# 28_Pins_Project_V1I2.net
KiCad netlist of a schematic drawn in Altium Designer
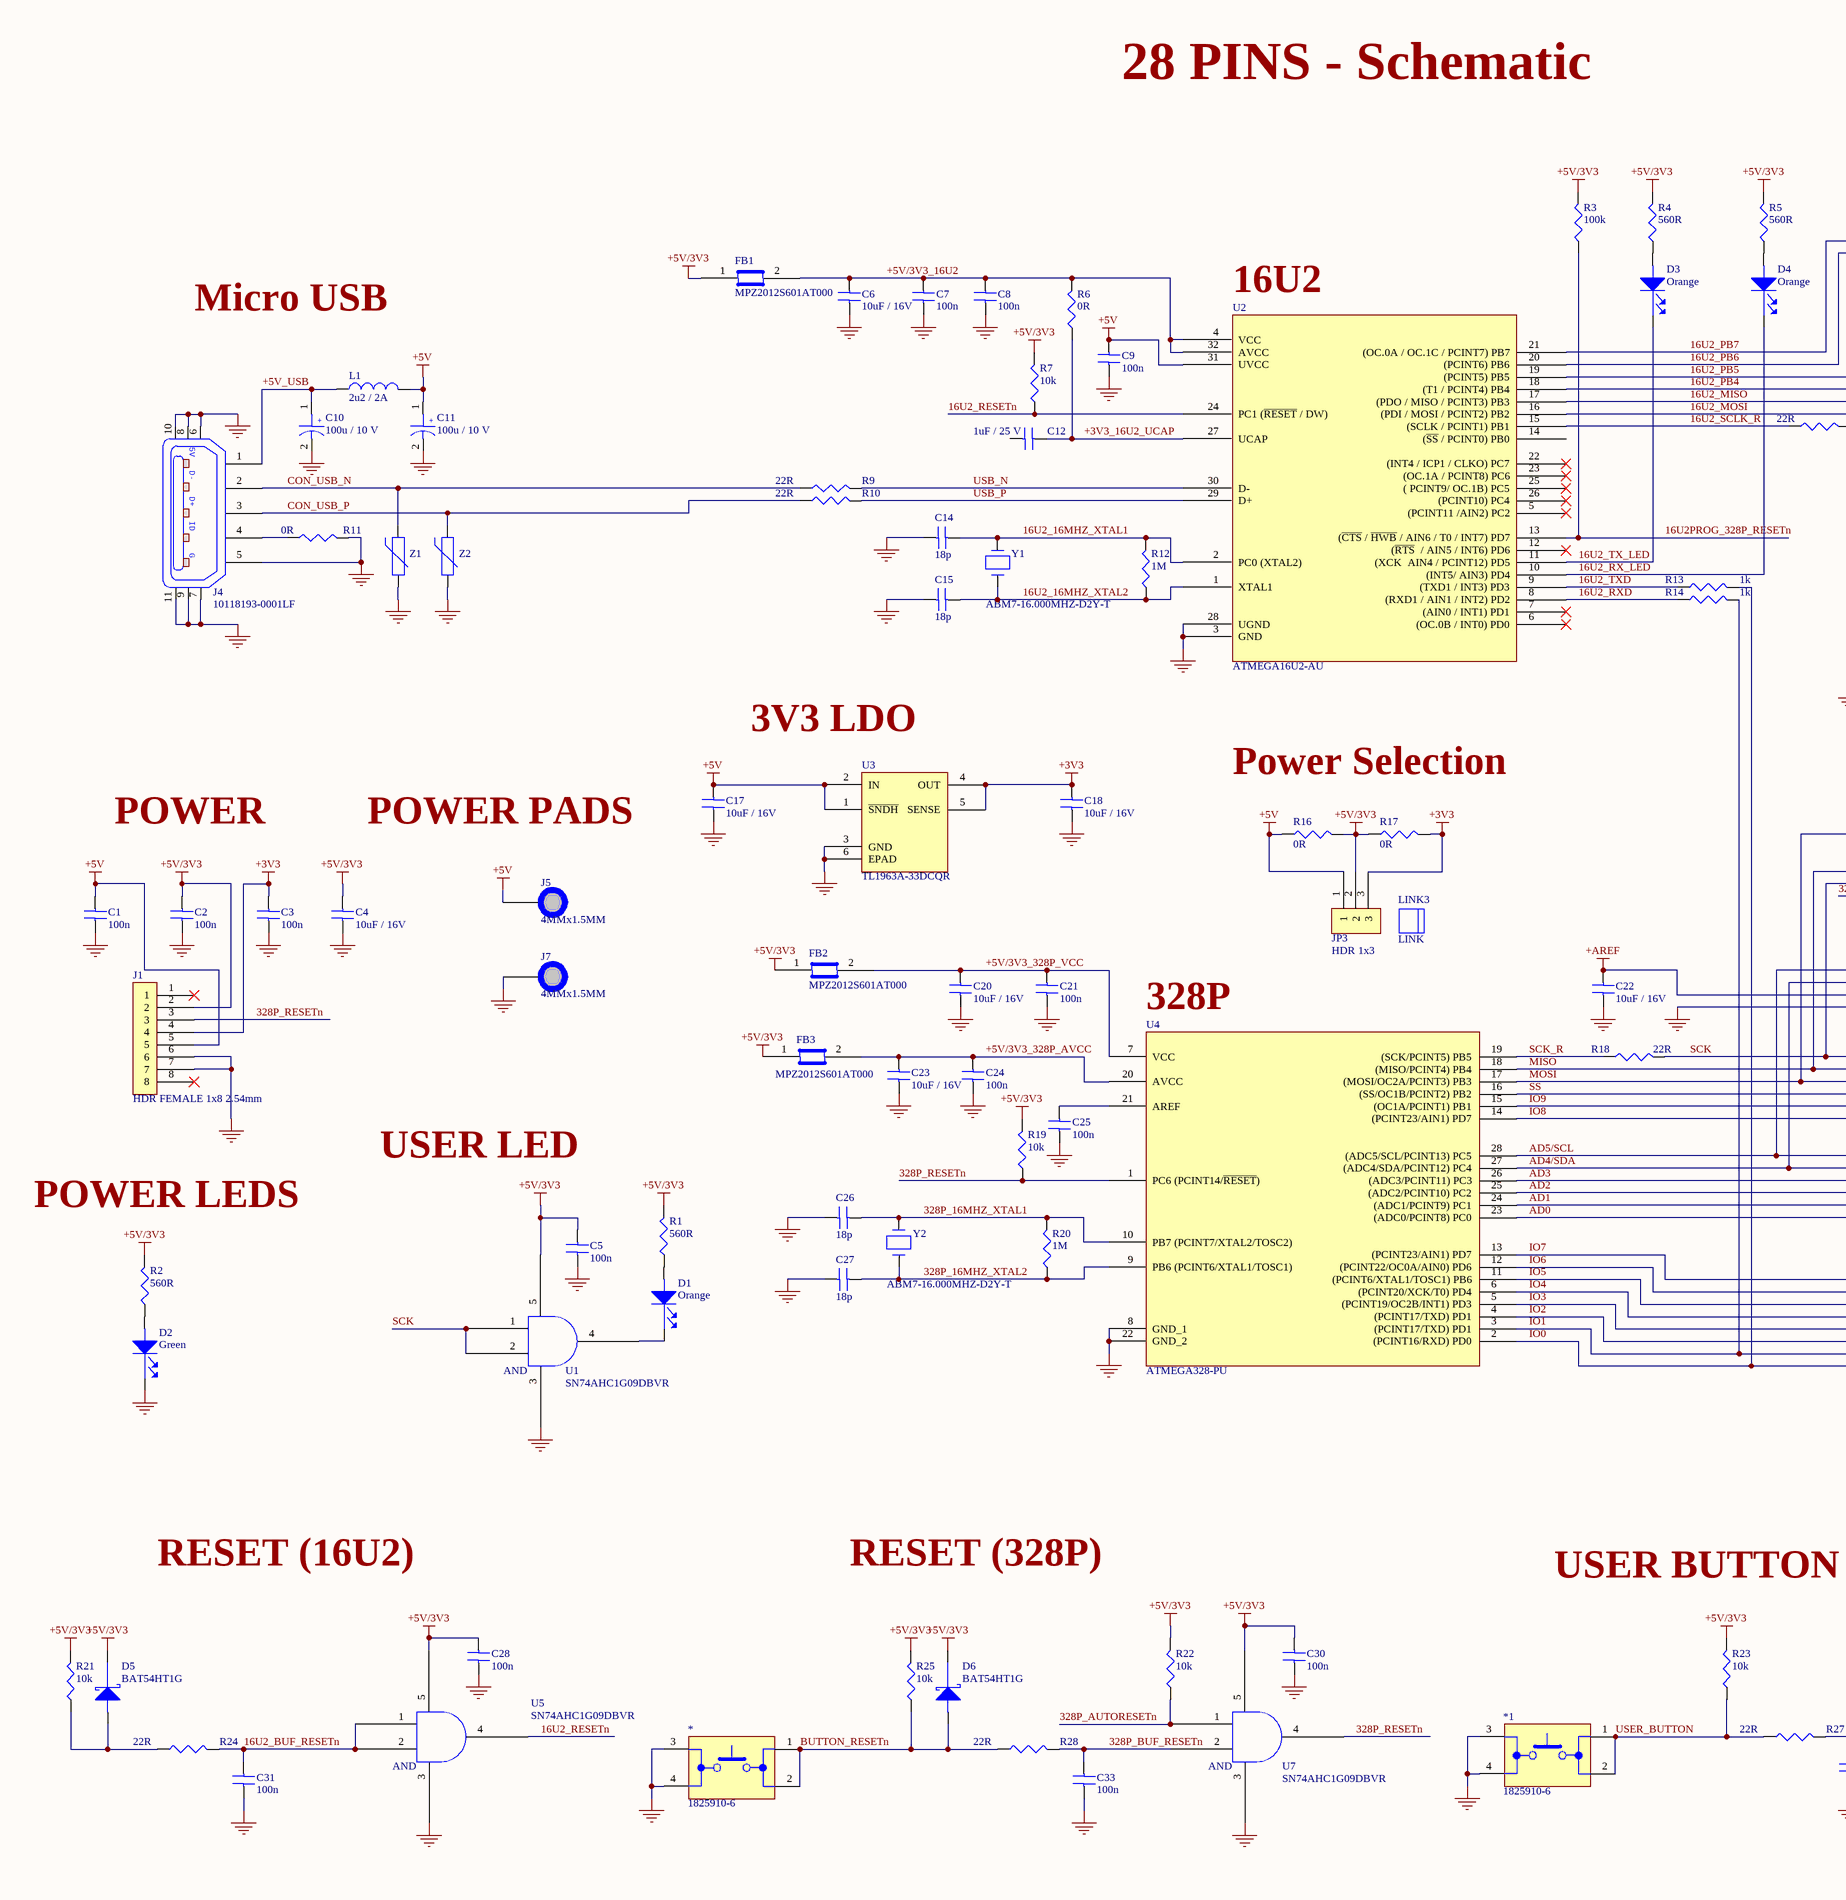
[diagram p0: 28_Pins_Project_V1I2.SchDoc, left]
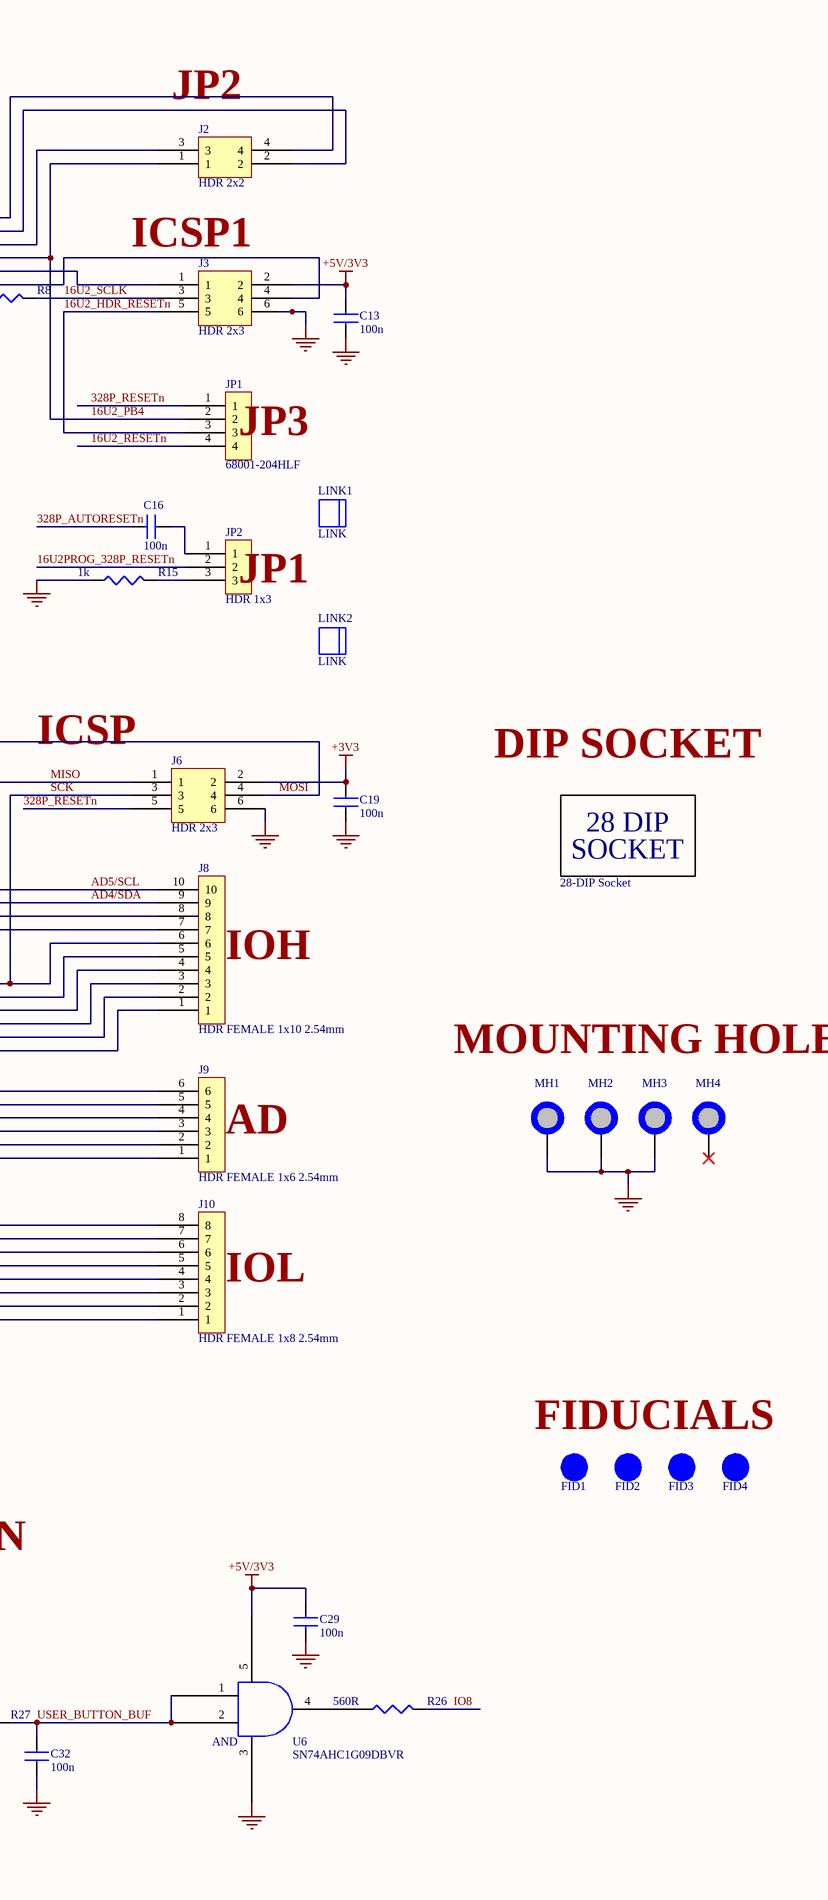
[diagram p1: 28_Pins_Project_V1I2.SchDoc, right]

(export (version "E")
  (design (tool "Eeschema 10.0.6"))
  (components
    (comp (ref "*")
      (value "1825910-6")
      (footprint "1825910-6")
      (description "6X6, H5,  160G TAC.SWITCH")
      (fields (field (name "MANUFACTURER") "TE Connectivity Alcoswitch"))
      (libsource (lib "28_Pins_Project_V1I2") (part "1825910-6"))
    )
    (comp (ref "*1")
      (value "1825910-6")
      (footprint "1825910-6")
      (description "6X6, H5,  160G TAC.SWITCH")
      (fields (field (name "MANUFACTURER") "TE Connectivity Alcoswitch"))
      (libsource (lib "28_Pins_Project_V1I2") (part "1825910-6"))
    )
    (comp (ref "C1")
      (value "100n")
      (footprint "C0805")
      (fields
        (field (name "MANUFACTURER") "TDK")
        (field (name "MANUFACTURER PART NUMBER") "C2012X7R1H104K085AA")
        (field (name "TOLERANCE") "10%")
      )
      (libsource (lib "28_Pins_Project_V1I2") (part "C2012X7R1H104K085AA"))
    )
    (comp (ref "C2")
      (value "100n")
      (footprint "C0805")
      (fields
        (field (name "MANUFACTURER") "TDK")
        (field (name "MANUFACTURER PART NUMBER") "C2012X7R1H104K085AA")
        (field (name "TOLERANCE") "10%")
      )
      (libsource (lib "28_Pins_Project_V1I2") (part "C2012X7R1H104K085AA"))
    )
    (comp (ref "C3")
      (value "100n")
      (footprint "C0805")
      (fields
        (field (name "MANUFACTURER") "TDK")
        (field (name "MANUFACTURER PART NUMBER") "C2012X7R1H104K085AA")
        (field (name "TOLERANCE") "10%")
      )
      (libsource (lib "28_Pins_Project_V1I2") (part "C2012X7R1H104K085AA"))
    )
    (comp (ref "C4")
      (value "10uF / 16V")
      (footprint "C0805")
      (fields
        (field (name "MANUFACTURER") "TDK")
        (field (name "MANUFACTURER PART NUMBER") "C2012X5R1C106M125AC")
        (field (name "TOLERANCE") "20%")
      )
      (libsource (lib "28_Pins_Project_V1I2") (part "C2012X5R1C106M125AC"))
    )
    (comp (ref "C5")
      (value "100n")
      (footprint "C0805")
      (fields
        (field (name "MANUFACTURER") "TDK")
        (field (name "MANUFACTURER PART NUMBER") "C2012X7R1H104K085AA")
        (field (name "TOLERANCE") "10%")
      )
      (libsource (lib "28_Pins_Project_V1I2") (part "C2012X7R1H104K085AA"))
    )
    (comp (ref "C6")
      (value "10uF / 16V")
      (footprint "C0805")
      (fields
        (field (name "MANUFACTURER") "TDK")
        (field (name "MANUFACTURER PART NUMBER") "C2012X5R1C106M125AC")
        (field (name "TOLERANCE") "20%")
      )
      (libsource (lib "28_Pins_Project_V1I2") (part "C2012X5R1C106M125AC"))
    )
    (comp (ref "C7")
      (value "100n")
      (footprint "C0805")
      (fields
        (field (name "MANUFACTURER") "TDK")
        (field (name "MANUFACTURER PART NUMBER") "C2012X7R1H104K085AA")
        (field (name "TOLERANCE") "10%")
      )
      (libsource (lib "28_Pins_Project_V1I2") (part "C2012X7R1H104K085AA"))
    )
    (comp (ref "C8")
      (value "100n")
      (footprint "C0805")
      (fields
        (field (name "MANUFACTURER") "TDK")
        (field (name "MANUFACTURER PART NUMBER") "C2012X7R1H104K085AA")
        (field (name "TOLERANCE") "10%")
      )
      (libsource (lib "28_Pins_Project_V1I2") (part "C2012X7R1H104K085AA"))
    )
    (comp (ref "C9")
      (value "100n")
      (footprint "C0805")
      (fields
        (field (name "MANUFACTURER") "TDK")
        (field (name "MANUFACTURER PART NUMBER") "C2012X7R1H104K085AA")
        (field (name "TOLERANCE") "10%")
      )
      (libsource (lib "28_Pins_Project_V1I2") (part "C2012X7R1H104K085AA"))
    )
    (comp (ref "C10")
      (value "100u / 10 V")
      (footprint "C_ALU_C_SIZE")
      (description "CAP ALUM 100UF 20% 10V SMD")
      (fields
        (field (name "MANUFACTURER") "Panasonic")
        (field (name "MANUFACTURER PART NUMBER") "EEE-1AA101WR")
      )
      (libsource (lib "28_Pins_Project_V1I2") (part "EEE-1AA101WR"))
    )
    (comp (ref "C11")
      (value "100u / 10 V")
      (footprint "C_ALU_C_SIZE")
      (description "CAP ALUM 100UF 20% 10V SMD")
      (fields
        (field (name "MANUFACTURER") "Panasonic")
        (field (name "MANUFACTURER PART NUMBER") "EEE-1AA101WR")
      )
      (libsource (lib "28_Pins_Project_V1I2") (part "EEE-1AA101WR"))
    )
    (comp (ref "C12")
      (value "1uF / 25 V")
      (footprint "C0805")
      (fields
        (field (name "MANUFACTURER") "TDK")
        (field (name "MANUFACTURER PART NUMBER") "C2012X5R1E105K125AA")
        (field (name "TOLERANCE") "10%")
      )
      (libsource (lib "28_Pins_Project_V1I2") (part "C2012X5R1E105K125AA"))
    )
    (comp (ref "C13")
      (value "100n")
      (footprint "C0805")
      (fields
        (field (name "MANUFACTURER") "TDK")
        (field (name "MANUFACTURER PART NUMBER") "C2012X7R1H104K085AA")
        (field (name "TOLERANCE") "10%")
      )
      (libsource (lib "28_Pins_Project_V1I2") (part "C2012X7R1H104K085AA"))
    )
    (comp (ref "C14")
      (value "18p")
      (footprint "C0805")
      (description "CAP CER 18PF 50V C0G/NP0 0805")
      (fields
        (field (name "MANUFACTURER") "KEMET")
        (field (name "MANUFACTURER PART NUMBER") "C0805C180J5GACTU")
      )
      (libsource (lib "28_Pins_Project_V1I2") (part "C0805C180J5GACTU"))
    )
    (comp (ref "C15")
      (value "18p")
      (footprint "C0805")
      (description "CAP CER 18PF 50V C0G/NP0 0805")
      (fields
        (field (name "MANUFACTURER") "KEMET")
        (field (name "MANUFACTURER PART NUMBER") "C0805C180J5GACTU")
      )
      (libsource (lib "28_Pins_Project_V1I2") (part "C0805C180J5GACTU"))
    )
    (comp (ref "C16")
      (value "100n")
      (footprint "C0805")
      (fields
        (field (name "MANUFACTURER") "TDK")
        (field (name "MANUFACTURER PART NUMBER") "C2012X7R1H104K085AA")
        (field (name "TOLERANCE") "10%")
      )
      (libsource (lib "28_Pins_Project_V1I2") (part "C2012X7R1H104K085AA"))
    )
    (comp (ref "C17")
      (value "10uF / 16V")
      (footprint "C0805")
      (fields
        (field (name "MANUFACTURER") "TDK")
        (field (name "MANUFACTURER PART NUMBER") "C2012X5R1C106M125AC")
        (field (name "TOLERANCE") "20%")
      )
      (libsource (lib "28_Pins_Project_V1I2") (part "C2012X5R1C106M125AC"))
    )
    (comp (ref "C18")
      (value "10uF / 16V")
      (footprint "C0805")
      (fields
        (field (name "MANUFACTURER") "TDK")
        (field (name "MANUFACTURER PART NUMBER") "C2012X5R1C106M125AC")
        (field (name "TOLERANCE") "20%")
      )
      (libsource (lib "28_Pins_Project_V1I2") (part "C2012X5R1C106M125AC"))
    )
    (comp (ref "C19")
      (value "100n")
      (footprint "C0805")
      (fields
        (field (name "MANUFACTURER") "TDK")
        (field (name "MANUFACTURER PART NUMBER") "C2012X7R1H104K085AA")
        (field (name "TOLERANCE") "10%")
      )
      (libsource (lib "28_Pins_Project_V1I2") (part "C2012X7R1H104K085AA"))
    )
    (comp (ref "C20")
      (value "10uF / 16V")
      (footprint "C0805")
      (fields
        (field (name "MANUFACTURER") "TDK")
        (field (name "MANUFACTURER PART NUMBER") "C2012X5R1C106M125AC")
        (field (name "TOLERANCE") "20%")
      )
      (libsource (lib "28_Pins_Project_V1I2") (part "C2012X5R1C106M125AC"))
    )
    (comp (ref "C21")
      (value "100n")
      (footprint "C0805")
      (fields
        (field (name "MANUFACTURER") "TDK")
        (field (name "MANUFACTURER PART NUMBER") "C2012X7R1H104K085AA")
        (field (name "TOLERANCE") "10%")
      )
      (libsource (lib "28_Pins_Project_V1I2") (part "C2012X7R1H104K085AA"))
    )
    (comp (ref "C22")
      (value "10uF / 16V")
      (footprint "C0805")
      (fields
        (field (name "MANUFACTURER") "TDK")
        (field (name "MANUFACTURER PART NUMBER") "C2012X5R1C106M125AC")
        (field (name "TOLERANCE") "20%")
      )
      (libsource (lib "28_Pins_Project_V1I2") (part "C2012X5R1C106M125AC"))
    )
    (comp (ref "C23")
      (value "10uF / 16V")
      (footprint "C0805")
      (fields
        (field (name "MANUFACTURER") "TDK")
        (field (name "MANUFACTURER PART NUMBER") "C2012X5R1C106M125AC")
        (field (name "TOLERANCE") "20%")
      )
      (libsource (lib "28_Pins_Project_V1I2") (part "C2012X5R1C106M125AC"))
    )
    (comp (ref "C24")
      (value "100n")
      (footprint "C0805")
      (fields
        (field (name "MANUFACTURER") "TDK")
        (field (name "MANUFACTURER PART NUMBER") "C2012X7R1H104K085AA")
        (field (name "TOLERANCE") "10%")
      )
      (libsource (lib "28_Pins_Project_V1I2") (part "C2012X7R1H104K085AA"))
    )
    (comp (ref "C25")
      (value "100n")
      (footprint "C0805")
      (fields
        (field (name "MANUFACTURER") "TDK")
        (field (name "MANUFACTURER PART NUMBER") "C2012X7R1H104K085AA")
        (field (name "TOLERANCE") "10%")
      )
      (libsource (lib "28_Pins_Project_V1I2") (part "C2012X7R1H104K085AA"))
    )
    (comp (ref "C26")
      (value "18p")
      (footprint "C0805")
      (description "CAP CER 18PF 50V C0G/NP0 0805")
      (fields
        (field (name "MANUFACTURER") "KEMET")
        (field (name "MANUFACTURER PART NUMBER") "C0805C180J5GACTU")
      )
      (libsource (lib "28_Pins_Project_V1I2") (part "C0805C180J5GACTU"))
    )
    (comp (ref "C27")
      (value "18p")
      (footprint "C0805")
      (description "CAP CER 18PF 50V C0G/NP0 0805")
      (fields
        (field (name "MANUFACTURER") "KEMET")
        (field (name "MANUFACTURER PART NUMBER") "C0805C180J5GACTU")
      )
      (libsource (lib "28_Pins_Project_V1I2") (part "C0805C180J5GACTU"))
    )
    (comp (ref "C28")
      (value "100n")
      (footprint "C0805")
      (fields
        (field (name "MANUFACTURER") "TDK")
        (field (name "MANUFACTURER PART NUMBER") "C2012X7R1H104K085AA")
        (field (name "TOLERANCE") "10%")
      )
      (libsource (lib "28_Pins_Project_V1I2") (part "C2012X7R1H104K085AA"))
    )
    (comp (ref "C29")
      (value "100n")
      (footprint "C0805")
      (fields
        (field (name "MANUFACTURER") "TDK")
        (field (name "MANUFACTURER PART NUMBER") "C2012X7R1H104K085AA")
        (field (name "TOLERANCE") "10%")
      )
      (libsource (lib "28_Pins_Project_V1I2") (part "C2012X7R1H104K085AA"))
    )
    (comp (ref "C30")
      (value "100n")
      (footprint "C0805")
      (fields
        (field (name "MANUFACTURER") "TDK")
        (field (name "MANUFACTURER PART NUMBER") "C2012X7R1H104K085AA")
        (field (name "TOLERANCE") "10%")
      )
      (libsource (lib "28_Pins_Project_V1I2") (part "C2012X7R1H104K085AA"))
    )
    (comp (ref "C31")
      (value "100n")
      (footprint "C0805")
      (fields
        (field (name "MANUFACTURER") "TDK")
        (field (name "MANUFACTURER PART NUMBER") "C2012X7R1H104K085AA")
        (field (name "TOLERANCE") "10%")
      )
      (libsource (lib "28_Pins_Project_V1I2") (part "C2012X7R1H104K085AA"))
    )
    (comp (ref "C32")
      (value "100n")
      (footprint "C0805")
      (fields
        (field (name "MANUFACTURER") "TDK")
        (field (name "MANUFACTURER PART NUMBER") "C2012X7R1H104K085AA")
        (field (name "TOLERANCE") "10%")
      )
      (libsource (lib "28_Pins_Project_V1I2") (part "C2012X7R1H104K085AA"))
    )
    (comp (ref "C33")
      (value "100n")
      (footprint "C0805")
      (fields
        (field (name "MANUFACTURER") "TDK")
        (field (name "MANUFACTURER PART NUMBER") "C2012X7R1H104K085AA")
        (field (name "TOLERANCE") "10%")
      )
      (libsource (lib "28_Pins_Project_V1I2") (part "C2012X7R1H104K085AA"))
    )
    (comp (ref "D1")
      (value "Orange")
      (footprint "LED_0603")
      (description "OSRAM - LO L29K-H2K1-24-Z - SMARTLED 0603 ORANGE 55AC2374")
      (fields
        (field (name "MANUFACTURER") "Osram Opto")
        (field (name "MANUFACTURER PART NUMBER") "LOL29K-H2K1-24-Z")
      )
      (libsource (lib "28_Pins_Project_V1I2") (part "LOL29K-H2K1-24-Z"))
    )
    (comp (ref "D2")
      (value "Green")
      (footprint "LED_0603")
      (description "LED Uni-Color Green 572nm 2-Pin Chip 0603(1608Metric) T/R")
      (fields
        (field (name "MANUFACTURER") "Osram Opto")
        (field (name "MANUFACTURER PART NUMBER") "LGL29K-G2J1-24-Z")
      )
      (libsource (lib "28_Pins_Project_V1I2") (part "LGL29K-G2J1-24-Z"))
    )
    (comp (ref "D3")
      (value "Orange")
      (footprint "LED_0603")
      (description "OSRAM - LO L29K-H2K1-24-Z - SMARTLED 0603 ORANGE 55AC2374")
      (fields
        (field (name "MANUFACTURER") "Osram Opto")
        (field (name "MANUFACTURER PART NUMBER") "LOL29K-H2K1-24-Z")
      )
      (libsource (lib "28_Pins_Project_V1I2") (part "LOL29K-H2K1-24-Z"))
    )
    (comp (ref "D4")
      (value "Orange")
      (footprint "LED_0603")
      (description "OSRAM - LO L29K-H2K1-24-Z - SMARTLED 0603 ORANGE 55AC2374")
      (fields
        (field (name "MANUFACTURER") "Osram Opto")
        (field (name "MANUFACTURER PART NUMBER") "LOL29K-H2K1-24-Z")
      )
      (libsource (lib "28_Pins_Project_V1I2") (part "LOL29K-H2K1-24-Z"))
    )
    (comp (ref "D5")
      (value "BAT54HT1G")
      (footprint "SOD323")
      (description "Small Signal Schottky Diode, Single, 30 V, 200 Ma, 800 Mv, 600 Ma, 150 C")
      (fields (field (name "MANUFACTURER") "ON Semiconductor / Fairchild"))
      (libsource (lib "28_Pins_Project_V1I2") (part "BAT54HT1G"))
    )
    (comp (ref "D6")
      (value "BAT54HT1G")
      (footprint "SOD323")
      (description "Small Signal Schottky Diode, Single, 30 V, 200 Ma, 800 Mv, 600 Ma, 150 C")
      (fields (field (name "MANUFACTURER") "ON Semiconductor / Fairchild"))
      (libsource (lib "28_Pins_Project_V1I2") (part "BAT54HT1G"))
    )
    (comp (ref "FB1")
      (value "MPZ2012S601AT000")
      (footprint "C0805")
      (description "Ferrite Beads Multi-Layer Power 600Ohm 25% 100MHz 2A 100mOhm DCR 0805 T/R")
      (fields (field (name "MANUFACTURER") "TDK"))
      (libsource (lib "28_Pins_Project_V1I2") (part "MPZ2012S601AT000"))
    )
    (comp (ref "FB2")
      (value "MPZ2012S601AT000")
      (footprint "C0805")
      (description "Ferrite Beads Multi-Layer Power 600Ohm 25% 100MHz 2A 100mOhm DCR 0805 T/R")
      (fields (field (name "MANUFACTURER") "TDK"))
      (libsource (lib "28_Pins_Project_V1I2") (part "MPZ2012S601AT000"))
    )
    (comp (ref "FB3")
      (value "MPZ2012S601AT000")
      (footprint "C0805")
      (description "Ferrite Beads Multi-Layer Power 600Ohm 25% 100MHz 2A 100mOhm DCR 0805 T/R")
      (fields (field (name "MANUFACTURER") "TDK"))
      (libsource (lib "28_Pins_Project_V1I2") (part "MPZ2012S601AT000"))
    )
    (comp (ref "FID1")
      (value "FID_1MMC")
      (footprint "FID_40X120D")
      (description "Fiducial 40mil Diameter, 120mil Mask")
      (libsource (lib "28_Pins_Project_V1I2") (part "FID_1MMC"))
    )
    (comp (ref "FID2")
      (value "FID_1MMC")
      (footprint "FID_40X120D")
      (description "Fiducial 40mil Diameter, 120mil Mask")
      (libsource (lib "28_Pins_Project_V1I2") (part "FID_1MMC"))
    )
    (comp (ref "FID3")
      (value "FID_1MMC")
      (footprint "FID_40X120D")
      (description "Fiducial 40mil Diameter, 120mil Mask")
      (libsource (lib "28_Pins_Project_V1I2") (part "FID_1MMC"))
    )
    (comp (ref "FID4")
      (value "FID_1MMC")
      (footprint "FID_40X120D")
      (description "Fiducial 40mil Diameter, 120mil Mask")
      (libsource (lib "28_Pins_Project_V1I2") (part "FID_1MMC"))
    )
    (comp (ref "J1")
      (value "HDR FEMALE 1x8 2.54mm")
      (footprint "Hdr_Female_1x8_2.54mm")
      (description "08-WAY SIL VERT SOCKET L/FREE")
      (fields (field (name "MANUFACTURER") "Harwin") (field (name "MANUFACTURER PART NUMBER") "M20-7820842"))
      (libsource (lib "28_Pins_Project_V1I2") (part "M20-7820842"))
    )
    (comp (ref "J2")
      (value "HDR 2x2")
      (footprint "HDR 2x2 2.54mm")
      (description "CONN HEADER 4POS .100 STR 15AU")
      (fields
        (field (name "MANUFACTURER") "Amphenol ICC / FCI")
        (field (name "MANUFACTURER PART NUMBER") "68602-204HLF")
      )
      (libsource (lib "28_Pins_Project_V1I2") (part "68602-204HLF"))
    )
    (comp (ref "J3")
      (value "HDR 2x3")
      (footprint "HDR 2x3 2.54mm")
      (description "Conn Unshrouded Header HDR 6 POS 2.54mm Solder ST Top Entry Thru-Hole BergStik® Bulk")
      (fields
        (field (name "MANUFACTURER") "Amphenol ICC / FCI")
        (field (name "MANUFACTURER PART NUMBER") "67997-106HLF")
      )
      (libsource (lib "28_Pins_Project_V1I2") (part "67997-106HLF"))
    )
    (comp (ref "J4")
      (value "10118193-0001LF")
      (footprint "10118193")
      (description "CONN USB MICRO B RECPT SMT R/A")
      (fields (field (name "MANUFACTURER") "Amphenol ICC / FCI"))
      (libsource (lib "28_Pins_Project_V1I2") (part "10118193-0001LF"))
    )
    (comp (ref "J5")
      (value "4MMx1.5MM")
      (footprint "PAD_WITH_HOLE_4MMx1.5MM")
      (description "Pad with a hole 4mm x 1.5mm")
      (libsource (lib "28_Pins_Project_V1I2") (part "PAD_WITH_HOLE_4MM_1.5MM"))
    )
    (comp (ref "J6")
      (value "HDR 2x3")
      (footprint "HDR 2x3 2.54mm")
      (description "Conn Unshrouded Header HDR 6 POS 2.54mm Solder ST Top Entry Thru-Hole BergStik® Bulk")
      (fields
        (field (name "MANUFACTURER") "Amphenol ICC / FCI")
        (field (name "MANUFACTURER PART NUMBER") "67997-106HLF")
      )
      (libsource (lib "28_Pins_Project_V1I2") (part "67997-106HLF"))
    )
    (comp (ref "J7")
      (value "4MMx1.5MM")
      (footprint "PAD_WITH_HOLE_4MMx1.5MM")
      (description "Pad with a hole 4mm x 1.5mm")
      (libsource (lib "28_Pins_Project_V1I2") (part "PAD_WITH_HOLE_4MM_1.5MM"))
    )
    (comp (ref "J8")
      (value "HDR FEMALE 1x10 2.54mm")
      (fields (field (name "MANUFACTURER") "Harwin") (field (name "MANUFACTURER PART NUMBER") "M20-7821046"))
      (libsource (lib "28_Pins_Project_V1I2") (part "M20-7821046"))
    )
    (comp (ref "J9")
      (value "HDR FEMALE 1x6 2.54mm")
      (footprint "Hdr_Female_1x6_2.54mm")
      (description "06-WAY SIL VERT SOCKET L/FREE")
      (fields (field (name "MANUFACTURER") "Harwin") (field (name "MANUFACTURER PART NUMBER") "M20-7820646"))
      (libsource (lib "28_Pins_Project_V1I2") (part "M20-7820646"))
    )
    (comp (ref "J10")
      (value "HDR FEMALE 1x8 2.54mm")
      (footprint "Hdr_Female_1x8_2.54mm")
      (description "2.54mm (0.1\") Pitch SIL Vertical PC Tail Socket Assembly, selective gold + tin, 8 contacts")
      (fields (field (name "MANUFACTURER") "Harwin") (field (name "MANUFACTURER PART NUMBER") "M20-7820842"))
      (libsource (lib "") (part "M20-7820842_1"))
    )
    (comp (ref "JP1")
      (value "68001-204HLF")
      (footprint "Hdr_Female_1x4_2.54mm")
      (description "Board Connector, 4 Contact(s), 1 Row(s), Male, Straight, Solder Terminal")
      (fields (field (name "MANUFACTURER") "Amphenol ICC"))
      (libsource (lib "28_Pins_Project_V1I2") (part "68001-204HLF"))
    )
    (comp (ref "JP2")
      (value "HDR 1x3")
      (footprint "Hdr_Female_1x3_2.54mm")
      (fields
        (field (name "MANUFACTURER") "Amphenol ICC")
        (field (name "MANUFACTURER PART NUMBER") "68000-103HLF")
      )
      (libsource (lib "28_Pins_Project_V1I2") (part "68000-103HLF"))
    )
    (comp (ref "JP3")
      (value "HDR 1x3")
      (footprint "Hdr_Female_1x3_2.54mm")
      (fields
        (field (name "MANUFACTURER") "Amphenol ICC")
        (field (name "MANUFACTURER PART NUMBER") "68000-103HLF")
      )
      (libsource (lib "") (part "68000-103HLF_1"))
    )
    (comp (ref "L1")
      (value "2u2 / 2A")
      (footprint "C1210_IND")
      (description "KEMET         L1210R2R2MDWIT             Product Range:L-DWI Series")
      (fields
        (field (name "MANUFACTURER") "KEMET")
        (field (name "MANUFACTURER PART NUMBER") "L1210R2R2MDWIT")
      )
      (libsource (lib "28_Pins_Project_V1I2") (part "L1210R2R2MDWIT"))
    )
    (comp (ref "LINK1")
      (value "LINK")
      (description "CONN JUMPER SHORTING .100\" GOLD")
      (fields
        (field (name "MANUFACTURER") "Sullins")
        (field (name "MANUFACTURER PART NUMBER") "QPC02SXGN-RC")
      )
      (libsource (lib "28_Pins_Project_V1I2") (part "QPC02SXGN-RC"))
    )
    (comp (ref "LINK2")
      (value "LINK")
      (description "CONN JUMPER SHORTING .100\" GOLD")
      (fields
        (field (name "MANUFACTURER") "Sullins")
        (field (name "MANUFACTURER PART NUMBER") "QPC02SXGN-RC")
      )
      (libsource (lib "28_Pins_Project_V1I2") (part "QPC02SXGN-RC"))
    )
    (comp (ref "LINK3")
      (value "LINK")
      (description "CONN JUMPER SHORTING .100\" GOLD")
      (fields
        (field (name "MANUFACTURER") "Sullins")
        (field (name "MANUFACTURER PART NUMBER") "QPC02SXGN-RC")
      )
      (libsource (lib "28_Pins_Project_V1I2") (part "QPC02SXGN-RC"))
    )
    (comp (ref "MH1")
      (value "MH_7.4MMNC_3.2MMD")
      (footprint "MH_7.4MMD_3.2MMD_NON_COPPER_NPTH")
      (description "Hole 7.4mm Diameter (Non Copper), 3.2mm Drill NPTH")
      (libsource (lib "28_Pins_Project_V1I2") (part "MH_7.4MMNC_3.2MMD"))
    )
    (comp (ref "MH2")
      (value "MH_7.4MMNC_3.2MMD")
      (footprint "MH_7.4MMD_3.2MMD_NON_COPPER_NPTH")
      (description "Hole 7.4mm Diameter (Non Copper), 3.2mm Drill NPTH")
      (libsource (lib "28_Pins_Project_V1I2") (part "MH_7.4MMNC_3.2MMD"))
    )
    (comp (ref "MH3")
      (value "MH_7.4MMNC_3.2MMD")
      (footprint "MH_7.4MMD_3.2MMD_NON_COPPER_NPTH")
      (description "Hole 7.4mm Diameter (Non Copper), 3.2mm Drill NPTH")
      (libsource (lib "28_Pins_Project_V1I2") (part "MH_7.4MMNC_3.2MMD"))
    )
    (comp (ref "MH4")
      (value "MH_7.4MMNC_3.2MMD")
      (footprint "MH_7.4MMD_3.2MMD_NON_COPPER_NPTH")
      (description "Hole 7.4mm Diameter (Non Copper), 3.2mm Drill NPTH")
      (libsource (lib "28_Pins_Project_V1I2") (part "MH_7.4MMNC_3.2MMD"))
    )
    (comp (ref "R1")
      (value "560R")
      (footprint "R0805")
      (description "Surface Mount Thick Film Resistor, RC Series, 560 ohm, 125 mW, - 1%, 150 V, 0805 [2012 Metric]")
      (fields
        (field (name "MANUFACTURER") "Yageo")
        (field (name "MANUFACTURER PART NUMBER") "RC0805FR-07560RL")
      )
      (libsource (lib "28_Pins_Project_V1I2") (part "RC0805FR-07560RL"))
    )
    (comp (ref "R2")
      (value "560R")
      (footprint "R0805")
      (description "Surface Mount Thick Film Resistor, RC Series, 560 ohm, 125 mW, - 1%, 150 V, 0805 [2012 Metric]")
      (fields
        (field (name "MANUFACTURER") "Yageo")
        (field (name "MANUFACTURER PART NUMBER") "RC0805FR-07560RL")
      )
      (libsource (lib "28_Pins_Project_V1I2") (part "RC0805FR-07560RL"))
    )
    (comp (ref "R3")
      (value "100k")
      (footprint "R0805")
      (description "Res Thick Film 0805 100K Ohm 1% 1/8W ±100ppm/°C Molded SMD Paper T/R")
      (fields
        (field (name "MANUFACTURER") "Yageo")
        (field (name "MANUFACTURER PART NUMBER") "RC0805FR-07100KL")
      )
      (libsource (lib "28_Pins_Project_V1I2") (part "RC0805FR-07100KL"))
    )
    (comp (ref "R4")
      (value "560R")
      (footprint "R0805")
      (description "Surface Mount Thick Film Resistor, RC Series, 560 ohm, 125 mW, - 1%, 150 V, 0805 [2012 Metric]")
      (fields
        (field (name "MANUFACTURER") "Yageo")
        (field (name "MANUFACTURER PART NUMBER") "RC0805FR-07560RL")
      )
      (libsource (lib "28_Pins_Project_V1I2") (part "RC0805FR-07560RL"))
    )
    (comp (ref "R5")
      (value "560R")
      (footprint "R0805")
      (description "Surface Mount Thick Film Resistor, RC Series, 560 ohm, 125 mW, - 1%, 150 V, 0805 [2012 Metric]")
      (fields
        (field (name "MANUFACTURER") "Yageo")
        (field (name "MANUFACTURER PART NUMBER") "RC0805FR-07560RL")
      )
      (libsource (lib "28_Pins_Project_V1I2") (part "RC0805FR-07560RL"))
    )
    (comp (ref "R6")
      (value "0R")
      (footprint "R0805")
      (description "Surface Mount Thick Film Resistor, RC Series, 125 mW, - 5%, 150 V, 0805 [2012 Metric]")
      (fields
        (field (name "MANUFACTURER") "Yageo")
        (field (name "MANUFACTURER PART NUMBER") "RC0805JR-070RL")
      )
      (libsource (lib "28_Pins_Project_V1I2") (part "RC0805JR-070RL"))
    )
    (comp (ref "R7")
      (value "10k")
      (description "RES SMD 10K OHM 1% 1/8W 0805")
      (fields
        (field (name "MANUFACTURER") "Yageo")
        (field (name "MANUFACTURER PART NUMBER") "RC0805FR-0710KL")
      )
      (libsource (lib "28_Pins_Project_V1I2") (part "RC0805FR-0710KL"))
    )
    (comp (ref "R8")
      (value "22R")
      (footprint "R0805")
      (description "RES SMD 22 OHM 1% 1/8W 0805")
      (fields
        (field (name "MANUFACTURER") "Yageo")
        (field (name "MANUFACTURER PART NUMBER") "RC0805FR-0722RL")
      )
      (libsource (lib "28_Pins_Project_V1I2") (part "RC0805FR-0722RL"))
    )
    (comp (ref "R9")
      (value "22R")
      (footprint "R0805")
      (description "RES SMD 22 OHM 1% 1/8W 0805")
      (fields
        (field (name "MANUFACTURER") "Yageo")
        (field (name "MANUFACTURER PART NUMBER") "RC0805FR-0722RL")
      )
      (libsource (lib "28_Pins_Project_V1I2") (part "RC0805FR-0722RL"))
    )
    (comp (ref "R10")
      (value "22R")
      (footprint "R0805")
      (description "RES SMD 22 OHM 1% 1/8W 0805")
      (fields
        (field (name "MANUFACTURER") "Yageo")
        (field (name "MANUFACTURER PART NUMBER") "RC0805FR-0722RL")
      )
      (libsource (lib "28_Pins_Project_V1I2") (part "RC0805FR-0722RL"))
    )
    (comp (ref "R11")
      (value "0R")
      (footprint "R0805")
      (description "Surface Mount Thick Film Resistor, RC Series, 125 mW, - 5%, 150 V, 0805 [2012 Metric]")
      (fields
        (field (name "MANUFACTURER") "Yageo")
        (field (name "MANUFACTURER PART NUMBER") "RC0805JR-070RL")
      )
      (libsource (lib "28_Pins_Project_V1I2") (part "RC0805JR-070RL"))
    )
    (comp (ref "R12")
      (value "1M")
      (footprint "R0805")
      (fields
        (field (name "MANUFACTURER") "Yageo Phycomp")
        (field (name "MANUFACTURER PART NUMBER") "RC0805FR-071ML")
        (field (name "TOLERANCE") "1%")
      )
      (libsource (lib "28_Pins_Project_V1I2") (part "RC0805FR-071ML_1"))
    )
    (comp (ref "R13")
      (value "1k")
      (footprint "R0805")
      (description "RES SMD 1K OHM 1% 1/8W 0805")
      (fields
        (field (name "MANUFACTURER") "Yageo")
        (field (name "MANUFACTURER PART NUMBER") "RC0805FR-071KL")
      )
      (libsource (lib "28_Pins_Project_V1I2") (part "RC0805FR-071KL"))
    )
    (comp (ref "R14")
      (value "1k")
      (footprint "R0805")
      (description "RES SMD 1K OHM 1% 1/8W 0805")
      (fields
        (field (name "MANUFACTURER") "Yageo")
        (field (name "MANUFACTURER PART NUMBER") "RC0805FR-071KL")
      )
      (libsource (lib "28_Pins_Project_V1I2") (part "RC0805FR-071KL"))
    )
    (comp (ref "R15")
      (value "1k")
      (footprint "R0805")
      (description "RES SMD 1K OHM 1% 1/8W 0805")
      (fields
        (field (name "MANUFACTURER") "Yageo")
        (field (name "MANUFACTURER PART NUMBER") "RC0805FR-071KL")
      )
      (libsource (lib "28_Pins_Project_V1I2") (part "RC0805FR-071KL"))
    )
    (comp (ref "R16")
      (value "0R")
      (footprint "R0805")
      (description "Surface Mount Thick Film Resistor, RC Series, 125 mW, - 5%, 150 V, 0805 [2012 Metric]")
      (fields
        (field (name "MANUFACTURER") "Yageo")
        (field (name "MANUFACTURER PART NUMBER") "RC0805JR-070RL")
      )
      (libsource (lib "28_Pins_Project_V1I2") (part "RC0805JR-070RL"))
    )
    (comp (ref "R17")
      (value "0R")
      (footprint "R0805")
      (description "Surface Mount Thick Film Resistor, RC Series, 125 mW, - 5%, 150 V, 0805 [2012 Metric]")
      (fields
        (field (name "MANUFACTURER") "Yageo")
        (field (name "MANUFACTURER PART NUMBER") "RC0805JR-070RL")
      )
      (libsource (lib "28_Pins_Project_V1I2") (part "RC0805JR-070RL"))
    )
    (comp (ref "R18")
      (value "22R")
      (footprint "R0805")
      (description "RES SMD 22 OHM 1% 1/8W 0805")
      (fields
        (field (name "MANUFACTURER") "Yageo")
        (field (name "MANUFACTURER PART NUMBER") "RC0805FR-0722RL")
      )
      (libsource (lib "28_Pins_Project_V1I2") (part "RC0805FR-0722RL"))
    )
    (comp (ref "R19")
      (value "10k")
      (description "RES SMD 10K OHM 1% 1/8W 0805")
      (fields
        (field (name "MANUFACTURER") "Yageo")
        (field (name "MANUFACTURER PART NUMBER") "RC0805FR-0710KL")
      )
      (libsource (lib "28_Pins_Project_V1I2") (part "RC0805FR-0710KL"))
    )
    (comp (ref "R20")
      (value "1M")
      (footprint "R0805")
      (fields
        (field (name "MANUFACTURER") "Yageo Phycomp")
        (field (name "MANUFACTURER PART NUMBER") "RC0805FR-071ML")
        (field (name "TOLERANCE") "1%")
      )
      (libsource (lib "28_Pins_Project_V1I2") (part "RC0805FR-071ML_1"))
    )
    (comp (ref "R21")
      (value "10k")
      (description "RES SMD 10K OHM 1% 1/8W 0805")
      (fields
        (field (name "MANUFACTURER") "Yageo")
        (field (name "MANUFACTURER PART NUMBER") "RC0805FR-0710KL")
      )
      (libsource (lib "28_Pins_Project_V1I2") (part "RC0805FR-0710KL"))
    )
    (comp (ref "R22")
      (value "10k")
      (description "RES SMD 10K OHM 1% 1/8W 0805")
      (fields
        (field (name "MANUFACTURER") "Yageo")
        (field (name "MANUFACTURER PART NUMBER") "RC0805FR-0710KL")
      )
      (libsource (lib "28_Pins_Project_V1I2") (part "RC0805FR-0710KL"))
    )
    (comp (ref "R23")
      (value "10k")
      (description "RES SMD 10K OHM 1% 1/8W 0805")
      (fields
        (field (name "MANUFACTURER") "Yageo")
        (field (name "MANUFACTURER PART NUMBER") "RC0805FR-0710KL")
      )
      (libsource (lib "28_Pins_Project_V1I2") (part "RC0805FR-0710KL"))
    )
    (comp (ref "R24")
      (value "22R")
      (footprint "R0805")
      (description "RES SMD 22 OHM 1% 1/8W 0805")
      (fields
        (field (name "MANUFACTURER") "Yageo")
        (field (name "MANUFACTURER PART NUMBER") "RC0805FR-0722RL")
      )
      (libsource (lib "28_Pins_Project_V1I2") (part "RC0805FR-0722RL"))
    )
    (comp (ref "R25")
      (value "10k")
      (description "RES SMD 10K OHM 1% 1/8W 0805")
      (fields
        (field (name "MANUFACTURER") "Yageo")
        (field (name "MANUFACTURER PART NUMBER") "RC0805FR-0710KL")
      )
      (libsource (lib "28_Pins_Project_V1I2") (part "RC0805FR-0710KL"))
    )
    (comp (ref "R26")
      (value "560R")
      (footprint "R0805")
      (description "Surface Mount Thick Film Resistor, RC Series, 560 ohm, 125 mW, - 1%, 150 V, 0805 [2012 Metric]")
      (fields
        (field (name "MANUFACTURER") "Yageo")
        (field (name "MANUFACTURER PART NUMBER") "RC0805FR-07560RL")
      )
      (libsource (lib "28_Pins_Project_V1I2") (part "RC0805FR-07560RL"))
    )
    (comp (ref "R27")
      (value "22R")
      (footprint "R0805")
      (description "RES SMD 22 OHM 1% 1/8W 0805")
      (fields
        (field (name "MANUFACTURER") "Yageo")
        (field (name "MANUFACTURER PART NUMBER") "RC0805FR-0722RL")
      )
      (libsource (lib "28_Pins_Project_V1I2") (part "RC0805FR-0722RL"))
    )
    (comp (ref "R28")
      (value "22R")
      (footprint "R0805")
      (description "RES SMD 22 OHM 1% 1/8W 0805")
      (fields
        (field (name "MANUFACTURER") "Yageo")
        (field (name "MANUFACTURER PART NUMBER") "RC0805FR-0722RL")
      )
      (libsource (lib "28_Pins_Project_V1I2") (part "RC0805FR-0722RL"))
    )
    (comp (ref "SCKT FOR U1")
      (value "28-DIP Socket")
      (footprint "28_DIP_7.62mm_SOCKET")
      (description "CONN IC DIP SOCKET 28POS TIN")
      (fields (field (name "MANUFACTURER") "3M") (field (name "MANUFACTURER PART NUMBER") "4828-3004-CP"))
      (libsource (lib "28_Pins_Project_V1I2") (part "4828-3004-CP"))
    )
    (comp (ref "U1")
      (value "SN74AHC1G09DBVR")
      (footprint "DBV_SOT_23_5 - duplicate")
      (description "TEXAS INSTRUMENTS - SN74AHC1G09DBVR - AND Gate, 74AHC1G09, 2 Input, 2 V to 5.5 V, SOT-23-5")
      (fields (field (name "MANUFACTURER") "Texas Instruments"))
      (libsource (lib "28_Pins_Project_V1I2") (part "SN74AHC1G09DBVR"))
    )
    (comp (ref "U2")
      (value "ATMEGA16U2-AU")
      (footprint "TQFP32")
      (description "ATmega Series 16 KB Flash 512 B RAM 16 MHz 8-Bit Microcontroller - TQFP-32")
      (fields (field (name "MANUFACTURER") "Microchip / Atmel"))
      (libsource (lib "28_Pins_Project_V1I2") (part "ATMEGA16U2-AU"))
    )
    (comp (ref "U3")
      (value "TL1963A-33DCQR")
      (footprint "DCQ (R-PDSO-G6)")
      (description "IC REG LINEAR 3.3V 1.5A SOT223-6")
      (fields (field (name "MANUFACTURER") "Texas Instruments"))
      (libsource (lib "28_Pins_Project_V1I2") (part "TL1963A-33DCQR"))
    )
    (comp (ref "U4")
      (value "ATMEGA328-PU")
      (footprint "28_DIP_7.62mm")
      (description "MCU 8-bit ATmega AVR RISC 32KB Flash 2.5V/3.3V/5V 28-Pin PDIP")
      (fields (field (name "MANUFACTURER") "Microchip / Atmel"))
      (libsource (lib "28_Pins_Project_V1I2") (part "ATMEGA328-PU"))
    )
    (comp (ref "U5")
      (value "SN74AHC1G09DBVR")
      (footprint "DBV_SOT_23_5 - duplicate")
      (description "TEXAS INSTRUMENTS - SN74AHC1G09DBVR - AND Gate, 74AHC1G09, 2 Input, 2 V to 5.5 V, SOT-23-5")
      (fields (field (name "MANUFACTURER") "Texas Instruments"))
      (libsource (lib "28_Pins_Project_V1I2") (part "SN74AHC1G09DBVR"))
    )
    (comp (ref "U6")
      (value "SN74AHC1G09DBVR")
      (footprint "DBV_SOT_23_5 - duplicate")
      (description "TEXAS INSTRUMENTS - SN74AHC1G09DBVR - AND Gate, 74AHC1G09, 2 Input, 2 V to 5.5 V, SOT-23-5")
      (fields (field (name "MANUFACTURER") "Texas Instruments"))
      (libsource (lib "28_Pins_Project_V1I2") (part "SN74AHC1G09DBVR"))
    )
    (comp (ref "U7")
      (value "SN74AHC1G09DBVR")
      (footprint "DBV_SOT_23_5 - duplicate")
      (description "TEXAS INSTRUMENTS - SN74AHC1G09DBVR - AND Gate, 74AHC1G09, 2 Input, 2 V to 5.5 V, SOT-23-5")
      (fields (field (name "MANUFACTURER") "Texas Instruments"))
      (libsource (lib "28_Pins_Project_V1I2") (part "SN74AHC1G09DBVR"))
    )
    (comp (ref "Y1")
      (value "ABM7-16.000MHZ-D2Y-T")
      (footprint "ABM7_v1_1_BIG")
      (description "CRYSTAL 16.0000MHZ 18PF SMD")
      (fields (field (name "MANUFACTURER") "Abracon") (field (name "TOLERANCE") "20ppm"))
      (libsource (lib "28_Pins_Project_V1I2") (part "ABM7-16.000MHZ-D2Y-T"))
    )
    (comp (ref "Y2")
      (value "ABM7-16.000MHZ-D2Y-T")
      (footprint "ABM7_v1_1_BIG")
      (description "CRYSTAL 16.0000MHZ 18PF SMD")
      (fields (field (name "MANUFACTURER") "Abracon") (field (name "TOLERANCE") "20ppm"))
      (libsource (lib "28_Pins_Project_V1I2") (part "ABM7-16.000MHZ-D2Y-T"))
    )
    (comp (ref "Z1")
      (value "CG0603MLC-05E")
      (footprint "R0603")
      (description "VARISTOR 0603")
      (fields (field (name "MANUFACTURER") "Bourns") (field (name "VOLTAGE") "5V"))
      (libsource (lib "28_Pins_Project_V1I2") (part "CG0603MLC-05E"))
    )
    (comp (ref "Z2")
      (value "CG0603MLC-05E")
      (footprint "R0603")
      (description "VARISTOR 0603")
      (fields (field (name "MANUFACTURER") "Bourns") (field (name "VOLTAGE") "5V"))
      (libsource (lib "28_Pins_Project_V1I2") (part "CG0603MLC-05E"))
    )
  )
  (nets
    (net (code "1") (name "+3V3") (class "Default")
      (node (ref "C18") (pin "2") (pinfunction "2_2") (pintype "passive"))
      (node (ref "C19") (pin "2") (pinfunction "2_2") (pintype "passive"))
      (node (ref "C3") (pin "2") (pinfunction "2_2") (pintype "passive"))
      (node (ref "J1") (pin "4") (pinfunction "4_4") (pintype "passive"))
      (node (ref "J6") (pin "2") (pinfunction "2_2") (pintype "passive"))
      (node (ref "JP3") (pin "3") (pinfunction "3_3") (pintype "passive"))
      (node (ref "R17") (pin "2") (pinfunction "2_2") (pintype "passive"))
      (node (ref "U3") (pin "4") (pinfunction "OUT_4") (pintype "passive"))
      (node (ref "U3") (pin "5") (pinfunction "SENSE_5") (pintype "passive"))
    )
    (net (code "2") (name "+5V") (class "Default")
      (node (ref "C1") (pin "2") (pinfunction "2_2") (pintype "passive"))
      (node (ref "C11") (pin "1") (pinfunction "1_1") (pintype "passive"))
      (node (ref "C17") (pin "2") (pinfunction "2_2") (pintype "passive"))
      (node (ref "C9") (pin "2") (pinfunction "2_2") (pintype "passive"))
      (node (ref "J1") (pin "5") (pinfunction "5_5") (pintype "passive"))
      (node (ref "JP3") (pin "1") (pinfunction "1_1") (pintype "passive"))
      (node (ref "L1") (pin "2") (pinfunction "2_2") (pintype "passive"))
      (node (ref "R16") (pin "1") (pinfunction "1_1") (pintype "passive"))
      (node (ref "U2") (pin "31") (pinfunction "UVCC_31") (pintype "passive"))
      (node (ref "U3") (pin "1") (pinfunction "~{SNDH}_1") (pintype "passive"))
      (node (ref "U3") (pin "2") (pinfunction "IN_2") (pintype "passive"))
    )
    (net (code "3") (name "+5V{slash}3V3") (class "Default")
      (node (ref "C13") (pin "2") (pinfunction "2_2") (pintype "passive"))
      (node (ref "C2") (pin "2") (pinfunction "2_2") (pintype "passive"))
      (node (ref "C28") (pin "2") (pinfunction "2_2") (pintype "passive"))
      (node (ref "C29") (pin "2") (pinfunction "2_2") (pintype "passive"))
      (node (ref "C30") (pin "2") (pinfunction "2_2") (pintype "passive"))
      (node (ref "C4") (pin "2") (pinfunction "2_2") (pintype "passive"))
      (node (ref "C5") (pin "2") (pinfunction "2_2") (pintype "passive"))
      (node (ref "D5") (pin "1") (pinfunction "Cathode_1") (pintype "passive"))
      (node (ref "D6") (pin "1") (pinfunction "Cathode_1") (pintype "passive"))
      (node (ref "FB1") (pin "1") (pinfunction "1_1") (pintype "passive"))
      (node (ref "FB2") (pin "1") (pinfunction "1_1") (pintype "passive"))
      (node (ref "FB3") (pin "1") (pinfunction "1_1") (pintype "passive"))
      (node (ref "J1") (pin "2") (pinfunction "2_2") (pintype "passive"))
      (node (ref "J3") (pin "2") (pinfunction "2_2") (pintype "passive"))
      (node (ref "JP3") (pin "2") (pinfunction "2_2") (pintype "passive"))
      (node (ref "R1") (pin "2") (pinfunction "2_2") (pintype "passive"))
      (node (ref "R16") (pin "2") (pinfunction "2_2") (pintype "passive"))
      (node (ref "R17") (pin "1") (pinfunction "1_1") (pintype "passive"))
      (node (ref "R19") (pin "2") (pinfunction "2_2") (pintype "passive"))
      (node (ref "R2") (pin "2") (pinfunction "2_2") (pintype "passive"))
      (node (ref "R21") (pin "2") (pinfunction "2_2") (pintype "passive"))
      (node (ref "R22") (pin "2") (pinfunction "2_2") (pintype "passive"))
      (node (ref "R23") (pin "2") (pinfunction "2_2") (pintype "passive"))
      (node (ref "R25") (pin "2") (pinfunction "2_2") (pintype "passive"))
      (node (ref "R3") (pin "2") (pinfunction "2_2") (pintype "passive"))
      (node (ref "R4") (pin "2") (pinfunction "2_2") (pintype "passive"))
      (node (ref "R5") (pin "2") (pinfunction "2_2") (pintype "passive"))
      (node (ref "R7") (pin "2") (pinfunction "2_2") (pintype "passive"))
      (node (ref "U1") (pin "5") (pinfunction "5_5") (pintype "passive"))
      (node (ref "U5") (pin "5") (pinfunction "5_5") (pintype "passive"))
      (node (ref "U6") (pin "5") (pinfunction "5_5") (pintype "passive"))
      (node (ref "U7") (pin "5") (pinfunction "5_5") (pintype "passive"))
    )
    (net (code "4") (name "+AREF") (class "Default")
      (node (ref "C22") (pin "2") (pinfunction "2_2") (pintype "passive"))
      (node (ref "J8") (pin "8") (pinfunction "8_8") (pintype "passive"))
    )
    (net (code "5") (name "/+3V3_16U2_UCAP") (class "Default")
      (node (ref "C12") (pin "2") (pinfunction "2_2") (pintype "passive"))
      (node (ref "R6") (pin "1") (pinfunction "1_1") (pintype "passive"))
      (node (ref "U2") (pin "27") (pinfunction "UCAP_27") (pintype "passive"))
    )
    (net (code "6") (name "/+5V_USB") (class "Default")
      (node (ref "C10") (pin "1") (pinfunction "1_1") (pintype "passive"))
      (node (ref "J4") (pin "1") (pinfunction "1_1") (pintype "passive"))
      (node (ref "L1") (pin "1") (pinfunction "1_1") (pintype "passive"))
    )
    (net (code "7") (name "/+5V{slash}3V3_16U2") (class "Default")
      (node (ref "C6") (pin "2") (pinfunction "2_2") (pintype "passive"))
      (node (ref "C7") (pin "2") (pinfunction "2_2") (pintype "passive"))
      (node (ref "C8") (pin "2") (pinfunction "2_2") (pintype "passive"))
      (node (ref "FB1") (pin "2") (pinfunction "2_2") (pintype "passive"))
      (node (ref "R6") (pin "2") (pinfunction "2_2") (pintype "passive"))
      (node (ref "U2") (pin "32") (pinfunction "AVCC_32") (pintype "passive"))
      (node (ref "U2") (pin "4") (pinfunction "VCC_4") (pintype "passive"))
    )
    (net (code "8") (name "/+5V{slash}3V3_328P_AVCC") (class "Default")
      (node (ref "C23") (pin "2") (pinfunction "2_2") (pintype "passive"))
      (node (ref "C24") (pin "2") (pinfunction "2_2") (pintype "passive"))
      (node (ref "FB3") (pin "2") (pinfunction "2_2") (pintype "passive"))
      (node (ref "U4") (pin "20") (pinfunction "AVCC_20") (pintype "passive"))
    )
    (net (code "9") (name "/+5V{slash}3V3_328P_VCC") (class "Default")
      (node (ref "C20") (pin "2") (pinfunction "2_2") (pintype "passive"))
      (node (ref "C21") (pin "2") (pinfunction "2_2") (pintype "passive"))
      (node (ref "FB2") (pin "2") (pinfunction "2_2") (pintype "passive"))
      (node (ref "U4") (pin "7") (pinfunction "VCC_7") (pintype "passive"))
    )
    (net (code "10") (name "/16U2PROG_328P_RESETn") (class "Default")
      (node (ref "JP2") (pin "2") (pinfunction "2_2") (pintype "passive"))
      (node (ref "R3") (pin "1") (pinfunction "1_1") (pintype "passive"))
      (node (ref "U2") (pin "13") (pinfunction "(~{CTS}_/_~{HWB}_/_AIN6_/_T0_/_INT7)_PD7_13") (pintype "passive"))
    )
    (net (code "11") (name "/16U2_16MHZ_XTAL1") (class "Default")
      (node (ref "C14") (pin "2") (pinfunction "2_2") (pintype "passive"))
      (node (ref "R12") (pin "2") (pinfunction "2_2") (pintype "passive"))
      (node (ref "U2") (pin "2") (pinfunction "PC0_(XTAL2)_2") (pintype "passive"))
      (node (ref "Y1") (pin "2") (pinfunction "2_2") (pintype "passive"))
    )
    (net (code "12") (name "/16U2_16MHZ_XTAL2") (class "Default")
      (node (ref "C15") (pin "2") (pinfunction "2_2") (pintype "passive"))
      (node (ref "R12") (pin "1") (pinfunction "1_1") (pintype "passive"))
      (node (ref "U2") (pin "1") (pinfunction "XTAL1_1") (pintype "passive"))
      (node (ref "Y1") (pin "1") (pinfunction "1_1") (pintype "passive"))
    )
    (net (code "13") (name "/16U2_BUF_RESETn") (class "Default")
      (node (ref "C31") (pin "2") (pinfunction "2_2") (pintype "passive"))
      (node (ref "R24") (pin "2") (pinfunction "2_2") (pintype "passive"))
      (node (ref "U5") (pin "1") (pinfunction "1_1") (pintype "passive"))
      (node (ref "U5") (pin "2") (pinfunction "2_2") (pintype "passive"))
    )
    (net (code "14") (name "/16U2_HDR_RESETn") (class "Default")
      (node (ref "J3") (pin "5") (pinfunction "5_5") (pintype "passive"))
      (node (ref "JP1") (pin "3") (pinfunction "3_3") (pintype "passive"))
    )
    (net (code "15") (name "/16U2_MISO") (class "Default")
      (node (ref "J3") (pin "1") (pinfunction "1_1") (pintype "passive"))
      (node (ref "U2") (pin "17") (pinfunction "(PDO_/_MISO_/_PCINT3)_PB3_17") (pintype "passive"))
    )
    (net (code "16") (name "/16U2_MOSI") (class "Default")
      (node (ref "J3") (pin "4") (pinfunction "4_4") (pintype "passive"))
      (node (ref "U2") (pin "16") (pinfunction "(PDI_/_MOSI_/_PCINT2)_PB2_16") (pintype "passive"))
    )
    (net (code "17") (name "/16U2_PB4") (class "Default")
      (node (ref "J2") (pin "1") (pinfunction "1_1") (pintype "passive"))
      (node (ref "JP1") (pin "2") (pinfunction "2_2") (pintype "passive"))
      (node (ref "U2") (pin "18") (pinfunction "(T1_/_PCINT4)_PB4_18") (pintype "passive"))
    )
    (net (code "18") (name "/16U2_PB5") (class "Default")
      (node (ref "J2") (pin "3") (pinfunction "3_3") (pintype "passive"))
      (node (ref "U2") (pin "19") (pinfunction "(PCINT5)_PB5_19") (pintype "passive"))
    )
    (net (code "19") (name "/16U2_PB6") (class "Default")
      (node (ref "J2") (pin "2") (pinfunction "2_2") (pintype "passive"))
      (node (ref "U2") (pin "20") (pinfunction "(PCINT6)_PB6_20") (pintype "passive"))
    )
    (net (code "20") (name "/16U2_PB7") (class "Default")
      (node (ref "J2") (pin "4") (pinfunction "4_4") (pintype "passive"))
      (node (ref "U2") (pin "21") (pinfunction "(OC.0A_/_OC.1C_/_PCINT7)_PB7_21") (pintype "passive"))
    )
    (net (code "21") (name "/16U2_RESETn") (class "Default")
      (node (ref "JP1") (pin "4") (pinfunction "4_4") (pintype "passive"))
      (node (ref "R7") (pin "1") (pinfunction "1_1") (pintype "passive"))
      (node (ref "U2") (pin "24") (pinfunction "PC1_(~{RESET}_/_DW)_24") (pintype "passive"))
      (node (ref "U5") (pin "4") (pinfunction "4_4") (pintype "passive"))
    )
    (net (code "22") (name "/16U2_RXD") (class "Default")
      (node (ref "R14") (pin "1") (pinfunction "1_1") (pintype "passive"))
      (node (ref "U2") (pin "8") (pinfunction "(RXD1_/_AIN1_/_INT2)_PD2_8") (pintype "passive"))
    )
    (net (code "23") (name "/16U2_RX_LED") (class "Default")
      (node (ref "D4") (pin "1") (pinfunction "Cathode_1") (pintype "passive"))
      (node (ref "U2") (pin "10") (pinfunction "(INT5/_AIN3)_PD4_10") (pintype "passive"))
    )
    (net (code "24") (name "/16U2_SCLK") (class "Default")
      (node (ref "J3") (pin "3") (pinfunction "3_3") (pintype "passive"))
      (node (ref "R8") (pin "2") (pinfunction "2_2") (pintype "passive"))
    )
    (net (code "25") (name "/16U2_SCLK_R") (class "Default")
      (node (ref "R8") (pin "1") (pinfunction "1_1") (pintype "passive"))
      (node (ref "U2") (pin "15") (pinfunction "(SCLK_/_PCINT1)_PB1_15") (pintype "passive"))
    )
    (net (code "26") (name "/16U2_TXD") (class "Default")
      (node (ref "R13") (pin "1") (pinfunction "1_1") (pintype "passive"))
      (node (ref "U2") (pin "9") (pinfunction "(TXD1_/_INT3)_PD3_9") (pintype "passive"))
    )
    (net (code "27") (name "/16U2_TX_LED") (class "Default")
      (node (ref "D3") (pin "1") (pinfunction "Cathode_1") (pintype "passive"))
      (node (ref "U2") (pin "11") (pinfunction "(XCK__AIN4_/_PCINT12)_PD5_11") (pintype "passive"))
    )
    (net (code "28") (name "/328P_16MHZ_XTAL1") (class "Default")
      (node (ref "C26") (pin "2") (pinfunction "2_2") (pintype "passive"))
      (node (ref "R20") (pin "2") (pinfunction "2_2") (pintype "passive"))
      (node (ref "U4") (pin "10") (pinfunction "PB7_(PCINT7/XTAL2/TOSC2)_10") (pintype "passive"))
      (node (ref "Y2") (pin "2") (pinfunction "2_2") (pintype "passive"))
    )
    (net (code "29") (name "/328P_16MHZ_XTAL2") (class "Default")
      (node (ref "C27") (pin "2") (pinfunction "2_2") (pintype "passive"))
      (node (ref "R20") (pin "1") (pinfunction "1_1") (pintype "passive"))
      (node (ref "U4") (pin "9") (pinfunction "PB6_(PCINT6/XTAL1/TOSC1)_9") (pintype "passive"))
      (node (ref "Y2") (pin "1") (pinfunction "1_1") (pintype "passive"))
    )
    (net (code "30") (name "/328P_AUTORESETn") (class "Default")
      (node (ref "C16") (pin "1") (pinfunction "1_1") (pintype "passive"))
      (node (ref "R22") (pin "1") (pinfunction "1_1") (pintype "passive"))
      (node (ref "U7") (pin "1") (pinfunction "1_1") (pintype "passive"))
    )
    (net (code "31") (name "/328P_BUF_RESETn") (class "Default")
      (node (ref "C33") (pin "2") (pinfunction "2_2") (pintype "passive"))
      (node (ref "R28") (pin "2") (pinfunction "2_2") (pintype "passive"))
      (node (ref "U7") (pin "2") (pinfunction "2_2") (pintype "passive"))
    )
    (net (code "32") (name "/328P_RESETn") (class "Default")
      (node (ref "J1") (pin "3") (pinfunction "3_3") (pintype "passive"))
      (node (ref "J6") (pin "5") (pinfunction "5_5") (pintype "passive"))
      (node (ref "JP1") (pin "1") (pinfunction "1_1") (pintype "passive"))
      (node (ref "R19") (pin "1") (pinfunction "1_1") (pintype "passive"))
      (node (ref "U4") (pin "1") (pinfunction "PC6_(PCINT14/~{RESET})_1") (pintype "passive"))
      (node (ref "U7") (pin "4") (pinfunction "4_4") (pintype "passive"))
    )
    (net (code "33") (name "/AD0") (class "Default")
      (node (ref "J9") (pin "1") (pinfunction "1_1") (pintype "passive"))
      (node (ref "U4") (pin "23") (pinfunction "(ADC0/PCINT8)_PC0_23") (pintype "passive"))
    )
    (net (code "34") (name "/AD1") (class "Default")
      (node (ref "J9") (pin "2") (pinfunction "2_2") (pintype "passive"))
      (node (ref "U4") (pin "24") (pinfunction "(ADC1/PCINT9)_PC1_24") (pintype "passive"))
    )
    (net (code "35") (name "/AD2") (class "Default")
      (node (ref "J9") (pin "3") (pinfunction "3_3") (pintype "passive"))
      (node (ref "U4") (pin "25") (pinfunction "(ADC2/PCINT10)_PC2_25") (pintype "passive"))
    )
    (net (code "36") (name "/AD3") (class "Default")
      (node (ref "J9") (pin "4") (pinfunction "4_4") (pintype "passive"))
      (node (ref "U4") (pin "26") (pinfunction "(ADC3/PCINT11)_PC3_26") (pintype "passive"))
    )
    (net (code "37") (name "/AD4{slash}SDA") (class "Default")
      (node (ref "J8") (pin "9") (pinfunction "9_9") (pintype "passive"))
      (node (ref "J9") (pin "5") (pinfunction "5_5") (pintype "passive"))
      (node (ref "U4") (pin "27") (pinfunction "(ADC4/SDA/PCINT12)_PC4_27") (pintype "passive"))
    )
    (net (code "38") (name "/AD5{slash}SCL") (class "Default")
      (node (ref "J8") (pin "10") (pinfunction "10_10") (pintype "passive"))
      (node (ref "J9") (pin "6") (pinfunction "6_6") (pintype "passive"))
      (node (ref "U4") (pin "28") (pinfunction "(ADC5/SCL/PCINT13)_PC5_28") (pintype "passive"))
    )
    (net (code "39") (name "/BUTTON_RESETn") (class "Default")
      (node (ref "*") (pin "1") (pinfunction "1_1") (pintype "passive"))
      (node (ref "*") (pin "2") (pinfunction "2_2") (pintype "passive"))
      (node (ref "D6") (pin "2") (pinfunction "Anode_2") (pintype "passive"))
      (node (ref "R25") (pin "1") (pinfunction "1_1") (pintype "passive"))
      (node (ref "R28") (pin "1") (pinfunction "1_1") (pintype "passive"))
    )
    (net (code "40") (name "/CON_USB_N") (class "Default")
      (node (ref "J4") (pin "2") (pinfunction "2_2") (pintype "passive"))
      (node (ref "R9") (pin "1") (pinfunction "1_1") (pintype "passive"))
      (node (ref "Z1") (pin "2") (pinfunction "2_2") (pintype "passive"))
    )
    (net (code "41") (name "/CON_USB_P") (class "Default")
      (node (ref "J4") (pin "3") (pinfunction "3_3") (pintype "passive"))
      (node (ref "R10") (pin "1") (pinfunction "1_1") (pintype "passive"))
      (node (ref "Z2") (pin "2") (pinfunction "2_2") (pintype "passive"))
    )
    (net (code "42") (name "/IO0") (class "Default")
      (node (ref "J10") (pin "1") (pinfunction "1_1") (pintype "passive"))
      (node (ref "R13") (pin "2") (pinfunction "2_2") (pintype "passive"))
      (node (ref "U4") (pin "2") (pinfunction "(PCINT16/RXD)_PD0_2") (pintype "passive"))
    )
    (net (code "43") (name "/IO1") (class "Default")
      (node (ref "J10") (pin "2") (pinfunction "2_2") (pintype "passive"))
      (node (ref "R14") (pin "2") (pinfunction "2_2") (pintype "passive"))
      (node (ref "U4") (pin "3") (pinfunction "(PCINT17/TXD)_PD1_3") (pintype "passive"))
    )
    (net (code "44") (name "/IO2") (class "Default")
      (node (ref "J10") (pin "3") (pinfunction "3_3") (pintype "passive"))
      (node (ref "U4") (pin "4") (pinfunction "(PCINT17/TXD)_PD1_4") (pintype "passive"))
    )
    (net (code "45") (name "/IO3") (class "Default")
      (node (ref "J10") (pin "4") (pinfunction "4_4") (pintype "passive"))
      (node (ref "U4") (pin "5") (pinfunction "(PCINT19/OC2B/INT1)_PD3_5") (pintype "passive"))
    )
    (net (code "46") (name "/IO4") (class "Default")
      (node (ref "J10") (pin "5") (pinfunction "5_5") (pintype "passive"))
      (node (ref "U4") (pin "6") (pinfunction "(PCINT20/XCK/T0)_PD4_6") (pintype "passive"))
    )
    (net (code "47") (name "/IO5") (class "Default")
      (node (ref "J10") (pin "6") (pinfunction "6_6") (pintype "passive"))
      (node (ref "U4") (pin "11") (pinfunction "(PCINT6/XTAL1/TOSC1)_PB6_11") (pintype "passive"))
    )
    (net (code "48") (name "/IO6") (class "Default")
      (node (ref "J10") (pin "7") (pinfunction "7_7") (pintype "passive"))
      (node (ref "U4") (pin "12") (pinfunction "(PCINT22/OC0A/AIN0)_PD6_12") (pintype "passive"))
    )
    (net (code "49") (name "/IO7") (class "Default")
      (node (ref "J10") (pin "8") (pinfunction "8_8") (pintype "passive"))
      (node (ref "U4") (pin "13") (pinfunction "(PCINT23/AIN1)_PD7_13") (pintype "passive"))
    )
    (net (code "50") (name "/IO8") (class "Default")
      (node (ref "J8") (pin "1") (pinfunction "1_1") (pintype "passive"))
      (node (ref "R26") (pin "2") (pinfunction "2_2") (pintype "passive"))
      (node (ref "U4") (pin "14") (pinfunction "(PCINT23/AIN1)_PD7_14") (pintype "passive"))
    )
    (net (code "51") (name "/IO9") (class "Default")
      (node (ref "J8") (pin "2") (pinfunction "2_2") (pintype "passive"))
      (node (ref "U4") (pin "15") (pinfunction "(OC1A/PCINT1)_PB1_15") (pintype "passive"))
    )
    (net (code "52") (name "/MISO") (class "Default")
      (node (ref "J6") (pin "1") (pinfunction "1_1") (pintype "passive"))
      (node (ref "J8") (pin "5") (pinfunction "5_5") (pintype "passive"))
      (node (ref "U4") (pin "18") (pinfunction "(MISO/PCINT4)_PB4_18") (pintype "passive"))
    )
    (net (code "53") (name "/MOSI") (class "Default")
      (node (ref "J6") (pin "4") (pinfunction "4_4") (pintype "passive"))
      (node (ref "J8") (pin "4") (pinfunction "4_4") (pintype "passive"))
      (node (ref "U4") (pin "17") (pinfunction "(MOSI/OC2A/PCINT3)_PB3_17") (pintype "passive"))
    )
    (net (code "54") (name "/SCK") (class "Default")
      (node (ref "J6") (pin "3") (pinfunction "3_3") (pintype "passive"))
      (node (ref "J8") (pin "6") (pinfunction "6_6") (pintype "passive"))
      (node (ref "R18") (pin "2") (pinfunction "2_2") (pintype "passive"))
      (node (ref "U1") (pin "1") (pinfunction "1_1") (pintype "passive"))
      (node (ref "U1") (pin "2") (pinfunction "2_2") (pintype "passive"))
    )
    (net (code "55") (name "/SCK_R") (class "Default")
      (node (ref "R18") (pin "1") (pinfunction "1_1") (pintype "passive"))
      (node (ref "U4") (pin "19") (pinfunction "(SCK/PCINT5)_PB5_19") (pintype "passive"))
    )
    (net (code "56") (name "/SS") (class "Default")
      (node (ref "J8") (pin "3") (pinfunction "3_3") (pintype "passive"))
      (node (ref "U4") (pin "16") (pinfunction "(SS/OC1B/PCINT2)_PB2_16") (pintype "passive"))
    )
    (net (code "57") (name "/USB_N") (class "Default")
      (node (ref "R9") (pin "2") (pinfunction "2_2") (pintype "passive"))
      (node (ref "U2") (pin "30") (pinfunction "D-_30") (pintype "passive"))
    )
    (net (code "58") (name "/USB_P") (class "Default")
      (node (ref "R10") (pin "2") (pinfunction "2_2") (pintype "passive"))
      (node (ref "U2") (pin "29") (pinfunction "D+_29") (pintype "passive"))
    )
    (net (code "59") (name "/USER_BUTTON") (class "Default")
      (node (ref "*1") (pin "1") (pinfunction "1_1") (pintype "passive"))
      (node (ref "*1") (pin "2") (pinfunction "2_2") (pintype "passive"))
      (node (ref "R23") (pin "1") (pinfunction "1_1") (pintype "passive"))
      (node (ref "R27") (pin "1") (pinfunction "1_1") (pintype "passive"))
    )
    (net (code "60") (name "/USER_BUTTON_BUF") (class "Default")
      (node (ref "C32") (pin "2") (pinfunction "2_2") (pintype "passive"))
      (node (ref "R27") (pin "2") (pinfunction "2_2") (pintype "passive"))
      (node (ref "U6") (pin "1") (pinfunction "1_1") (pintype "passive"))
      (node (ref "U6") (pin "2") (pinfunction "2_2") (pintype "passive"))
    )
    (net (code "61") (name "GND") (class "Default")
      (node (ref "*") (pin "3") (pinfunction "3_3") (pintype "passive"))
      (node (ref "*") (pin "4") (pinfunction "4_4") (pintype "passive"))
      (node (ref "*1") (pin "3") (pinfunction "3_3") (pintype "passive"))
      (node (ref "*1") (pin "4") (pinfunction "4_4") (pintype "passive"))
      (node (ref "C1") (pin "1") (pinfunction "1_1") (pintype "passive"))
      (node (ref "C10") (pin "2") (pinfunction "2_2") (pintype "passive"))
      (node (ref "C11") (pin "2") (pinfunction "2_2") (pintype "passive"))
      (node (ref "C13") (pin "1") (pinfunction "1_1") (pintype "passive"))
      (node (ref "C14") (pin "1") (pinfunction "1_1") (pintype "passive"))
      (node (ref "C15") (pin "1") (pinfunction "1_1") (pintype "passive"))
      (node (ref "C17") (pin "1") (pinfunction "1_1") (pintype "passive"))
      (node (ref "C18") (pin "1") (pinfunction "1_1") (pintype "passive"))
      (node (ref "C19") (pin "1") (pinfunction "1_1") (pintype "passive"))
      (node (ref "C2") (pin "1") (pinfunction "1_1") (pintype "passive"))
      (node (ref "C20") (pin "1") (pinfunction "1_1") (pintype "passive"))
      (node (ref "C21") (pin "1") (pinfunction "1_1") (pintype "passive"))
      (node (ref "C22") (pin "1") (pinfunction "1_1") (pintype "passive"))
      (node (ref "C23") (pin "1") (pinfunction "1_1") (pintype "passive"))
      (node (ref "C24") (pin "1") (pinfunction "1_1") (pintype "passive"))
      (node (ref "C25") (pin "1") (pinfunction "1_1") (pintype "passive"))
      (node (ref "C26") (pin "1") (pinfunction "1_1") (pintype "passive"))
      (node (ref "C27") (pin "1") (pinfunction "1_1") (pintype "passive"))
      (node (ref "C28") (pin "1") (pinfunction "1_1") (pintype "passive"))
      (node (ref "C29") (pin "1") (pinfunction "1_1") (pintype "passive"))
      (node (ref "C3") (pin "1") (pinfunction "1_1") (pintype "passive"))
      (node (ref "C30") (pin "1") (pinfunction "1_1") (pintype "passive"))
      (node (ref "C31") (pin "1") (pinfunction "1_1") (pintype "passive"))
      (node (ref "C32") (pin "1") (pinfunction "1_1") (pintype "passive"))
      (node (ref "C33") (pin "1") (pinfunction "1_1") (pintype "passive"))
      (node (ref "C4") (pin "1") (pinfunction "1_1") (pintype "passive"))
      (node (ref "C5") (pin "1") (pinfunction "1_1") (pintype "passive"))
      (node (ref "C6") (pin "1") (pinfunction "1_1") (pintype "passive"))
      (node (ref "C7") (pin "1") (pinfunction "1_1") (pintype "passive"))
      (node (ref "C8") (pin "1") (pinfunction "1_1") (pintype "passive"))
      (node (ref "C9") (pin "1") (pinfunction "1_1") (pintype "passive"))
      (node (ref "D2") (pin "1") (pinfunction "Cathode_1") (pintype "passive"))
      (node (ref "J1") (pin "6") (pinfunction "6_6") (pintype "passive"))
      (node (ref "J1") (pin "7") (pinfunction "7_7") (pintype "passive"))
      (node (ref "J3") (pin "6") (pinfunction "6_6") (pintype "passive"))
      (node (ref "J4") (pin "10") (pinfunction "10_10") (pintype "passive"))
      (node (ref "J4") (pin "11") (pinfunction "11_11") (pintype "passive"))
      (node (ref "J4") (pin "5") (pinfunction "5_5") (pintype "passive"))
      (node (ref "J4") (pin "6") (pinfunction "6_6") (pintype "passive"))
      (node (ref "J4") (pin "7") (pinfunction "7_7") (pintype "passive"))
      (node (ref "J4") (pin "8") (pinfunction "8_8") (pintype "passive"))
      (node (ref "J4") (pin "9") (pinfunction "9_9") (pintype "passive"))
      (node (ref "J6") (pin "6") (pinfunction "6_6") (pintype "passive"))
      (node (ref "J8") (pin "7") (pinfunction "7_7") (pintype "passive"))
      (node (ref "MH1") (pin "1") (pinfunction "1_1") (pintype "passive"))
      (node (ref "MH2") (pin "1") (pinfunction "1_1") (pintype "passive"))
      (node (ref "MH3") (pin "1") (pinfunction "1_1") (pintype "passive"))
      (node (ref "R11") (pin "2") (pinfunction "2_2") (pintype "passive"))
      (node (ref "R15") (pin "1") (pinfunction "1_1") (pintype "passive"))
      (node (ref "U1") (pin "3") (pinfunction "3_3") (pintype "passive"))
      (node (ref "U2") (pin "28") (pinfunction "UGND_28") (pintype "passive"))
      (node (ref "U2") (pin "3") (pinfunction "GND_3") (pintype "passive"))
      (node (ref "U3") (pin "3") (pinfunction "GND_3") (pintype "passive"))
      (node (ref "U3") (pin "6") (pinfunction "EPAD_6") (pintype "passive"))
      (node (ref "U4") (pin "22") (pinfunction "GND_2_22") (pintype "passive"))
      (node (ref "U4") (pin "8") (pinfunction "GND_1_8") (pintype "passive"))
      (node (ref "U5") (pin "3") (pinfunction "3_3") (pintype "passive"))
      (node (ref "U6") (pin "3") (pinfunction "3_3") (pintype "passive"))
      (node (ref "U7") (pin "3") (pinfunction "3_3") (pintype "passive"))
      (node (ref "Z1") (pin "1") (pinfunction "1_1") (pintype "passive"))
      (node (ref "Z2") (pin "1") (pinfunction "1_1") (pintype "passive"))
    )
    (net (code "62") (name "Net-(C16-Pad2)") (class "Default")
      (node (ref "C16") (pin "2") (pinfunction "2_2") (pintype "passive"))
      (node (ref "JP2") (pin "1") (pinfunction "1_1") (pintype "passive"))
    )
    (net (code "63") (name "Net-(D1-Anode)") (class "Default")
      (node (ref "D1") (pin "2") (pinfunction "Anode_2") (pintype "passive"))
      (node (ref "R1") (pin "1") (pinfunction "1_1") (pintype "passive"))
    )
    (net (code "64") (name "Net-(D1-Cathode)") (class "Default")
      (node (ref "D1") (pin "1") (pinfunction "Cathode_1") (pintype "passive"))
      (node (ref "U1") (pin "4") (pinfunction "4_4") (pintype "passive"))
    )
    (net (code "65") (name "Net-(D2-Anode)") (class "Default")
      (node (ref "D2") (pin "2") (pinfunction "Anode_2") (pintype "passive"))
      (node (ref "R2") (pin "1") (pinfunction "1_1") (pintype "passive"))
    )
    (net (code "66") (name "Net-(D3-Anode)") (class "Default")
      (node (ref "D3") (pin "2") (pinfunction "Anode_2") (pintype "passive"))
      (node (ref "R4") (pin "1") (pinfunction "1_1") (pintype "passive"))
    )
    (net (code "67") (name "Net-(D4-Anode)") (class "Default")
      (node (ref "D4") (pin "2") (pinfunction "Anode_2") (pintype "passive"))
      (node (ref "R5") (pin "1") (pinfunction "1_1") (pintype "passive"))
    )
    (net (code "68") (name "Net-(D5-Anode)") (class "Default")
      (node (ref "D5") (pin "2") (pinfunction "Anode_2") (pintype "passive"))
      (node (ref "R21") (pin "1") (pinfunction "1_1") (pintype "passive"))
      (node (ref "R24") (pin "1") (pinfunction "1_1") (pintype "passive"))
    )
    (net (code "69") (name "Net-(J4-Pad4)") (class "Default")
      (node (ref "J4") (pin "4") (pinfunction "4_4") (pintype "passive"))
      (node (ref "R11") (pin "1") (pinfunction "1_1") (pintype "passive"))
    )
    (net (code "70") (name "Net-(JP2-Pad3)") (class "Default")
      (node (ref "JP2") (pin "3") (pinfunction "3_3") (pintype "passive"))
      (node (ref "R15") (pin "2") (pinfunction "2_2") (pintype "passive"))
    )
    (net (code "71") (name "Net-(R26-Pad1)") (class "Default")
      (node (ref "R26") (pin "1") (pinfunction "1_1") (pintype "passive"))
      (node (ref "U6") (pin "4") (pinfunction "4_4") (pintype "passive"))
    )
    (net (code "72") (name "Net-(U4-AREF)") (class "Default")
      (node (ref "C25") (pin "2") (pinfunction "2_2") (pintype "passive"))
      (node (ref "U4") (pin "21") (pinfunction "AREF_21") (pintype "passive"))
    )
    (net (code "73") (name "unconnected-(C12-Pad1)") (class "Default")
      (node (ref "C12") (pin "1") (pinfunction "1_1") (pintype "passive"))
    )
    (net (code "74") (name "unconnected-(J1-Pad1)") (class "Default")
      (node (ref "J1") (pin "1") (pinfunction "1_1") (pintype "passive+no_connect"))
    )
    (net (code "75") (name "unconnected-(J1-Pad8)") (class "Default")
      (node (ref "J1") (pin "8") (pinfunction "8_8") (pintype "passive+no_connect"))
    )
    (net (code "76") (name "unconnected-(J5-Pad1)") (class "Default")
      (node (ref "J5") (pin "1") (pinfunction "1_1") (pintype "passive"))
    )
    (net (code "77") (name "unconnected-(J7-Pad1)") (class "Default")
      (node (ref "J7") (pin "1") (pinfunction "1_1") (pintype "passive"))
    )
    (net (code "78") (name "unconnected-(MH4-Pad1)") (class "Default")
      (node (ref "MH4") (pin "1") (pinfunction "1_1") (pintype "passive+no_connect"))
    )
    (net (code "79") (name "unconnected-(U2-(AIN0_{slash}_INT1)_PD1-Pad7)") (class "Default")
      (node (ref "U2") (pin "7") (pinfunction "(AIN0_/_INT1)_PD1_7") (pintype "passive+no_connect"))
    )
    (net (code "80") (name "unconnected-(U2-(INT4_{slash}_ICP1_{slash}_CLKO)_PC7-Pad22)") (class "Default")
      (node (ref "U2") (pin "22") (pinfunction "(INT4_/_ICP1_/_CLKO)_PC7_22") (pintype "passive+no_connect"))
    )
    (net (code "81") (name "unconnected-(U2-(OC.0B_{slash}_INT0)_PD0-Pad6)") (class "Default")
      (node (ref "U2") (pin "6") (pinfunction "(OC.0B_/_INT0)_PD0_6") (pintype "passive+no_connect"))
    )
    (net (code "82") (name "unconnected-(U2-(OC.1A_{slash}_PCINT8)_PC6-Pad23)") (class "Default")
      (node (ref "U2") (pin "23") (pinfunction "(OC.1A_/_PCINT8)_PC6_23") (pintype "passive+no_connect"))
    )
    (net (code "83") (name "unconnected-(U2-(PCINT10)_PC4-Pad26)") (class "Default")
      (node (ref "U2") (pin "26") (pinfunction "(PCINT10)_PC4_26") (pintype "passive+no_connect"))
    )
    (net (code "84") (name "unconnected-(U2-(PCINT11_{slash}AIN2)_PC2-Pad5)") (class "Default")
      (node (ref "U2") (pin "5") (pinfunction "(PCINT11_/AIN2)_PC2_5") (pintype "passive+no_connect"))
    )
    (net (code "85") (name "unconnected-(U2-(_PCINT9{slash}_OC.1B)_PC5-Pad25)") (class "Default")
      (node (ref "U2") (pin "25") (pinfunction "(_PCINT9/_OC.1B)_PC5_25") (pintype "passive+no_connect"))
    )
    (net (code "86") (name "unconnected-(U2-(~{RTS}__{slash}_AIN5_{slash}_INT6)_PD6-Pad12)") (class "Default")
      (node (ref "U2") (pin "12") (pinfunction "(~{RTS}__/_AIN5_/_INT6)_PD6_12") (pintype "passive+no_connect"))
    )
    (net (code "87") (name "unconnected-(U2-(~{SS}_{slash}_PCINT0)_PB0-Pad14)") (class "Default")
      (node (ref "U2") (pin "14") (pinfunction "(~{SS}_/_PCINT0)_PB0_14") (pintype "passive"))
    )
  )
)
